# FM110236A.net
KiCad netlist of a schematic drawn in Altium Designer
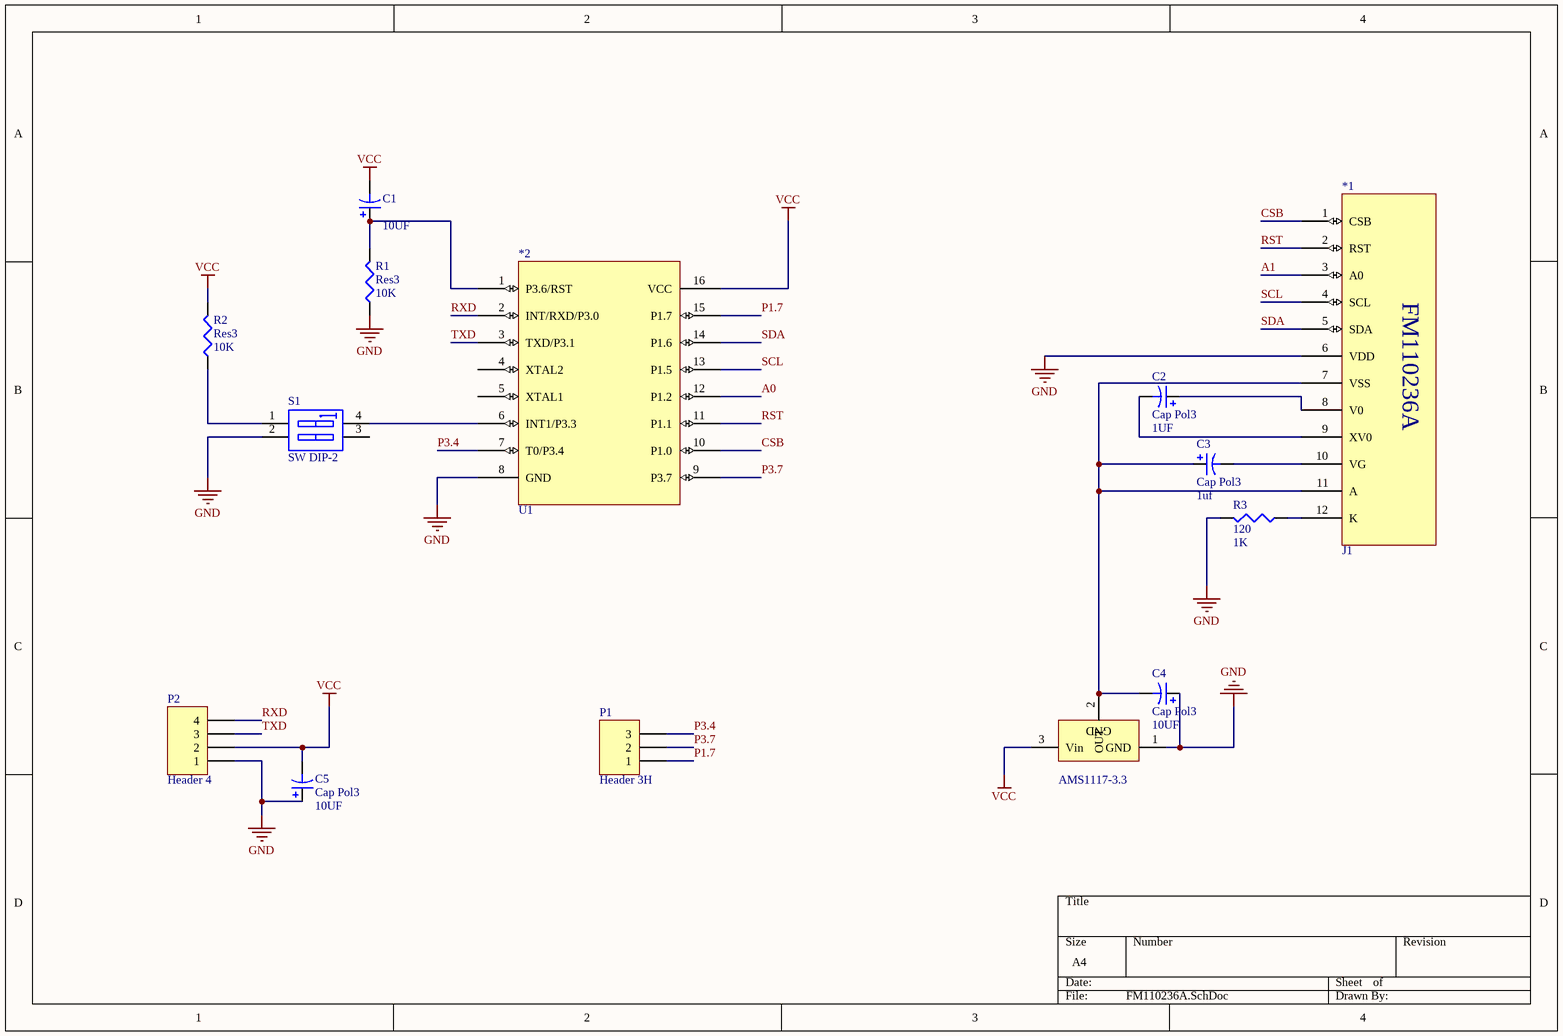
[diagram p0: FM110236A.SchDoc]

(export (version "E")
  (design (tool "Eeschema 10.0.6"))
  (components
    (comp (ref "*1")
      (value "J1")
      (footprint "PCBComponent_1")
      (libsource (lib "FM110236A") (part "Component_1"))
    )
    (comp (ref "*2")
      (value "U1")
      (footprint "TSOP127P620X160-16N")
      (libsource (lib "stc11f02") (part "Component_3"))
    )
    (comp (ref "C1")
      (value "10UF")
      (footprint "C0805")
      (description "Polarized Capacitor (Surface Mount)")
      (fields (field (name "PUBLISHER") "Altium Limited"))
      (libsource (lib "Miscellaneous Devices") (part "Cap Pol3"))
    )
    (comp (ref "C2")
      (value "Cap Pol3")
      (footprint "C0805")
      (description "Polarized Capacitor (Surface Mount)")
      (fields (field (name "ALTIUM_VALUE") "1UF") (field (name "PUBLISHER") "Altium Limited"))
      (libsource (lib "Miscellaneous Devices") (part "Cap Pol3"))
    )
    (comp (ref "C3")
      (value "Cap Pol3")
      (footprint "C0805")
      (description "Polarized Capacitor (Surface Mount)")
      (fields (field (name "ALTIUM_VALUE") "1uf") (field (name "PUBLISHER") "Altium Limited"))
      (libsource (lib "Miscellaneous Devices") (part "Cap Pol3"))
    )
    (comp (ref "C4")
      (value "Cap Pol3")
      (footprint "C0805")
      (description "Polarized Capacitor (Surface Mount)")
      (fields (field (name "ALTIUM_VALUE") "10UF") (field (name "PUBLISHER") "Altium Limited"))
      (libsource (lib "Miscellaneous Devices") (part "Cap Pol3"))
    )
    (comp (ref "C5")
      (value "Cap Pol3")
      (footprint "C0805")
      (description "Polarized Capacitor (Surface Mount)")
      (fields (field (name "ALTIUM_VALUE") "10UF") (field (name "PUBLISHER") "Altium Limited"))
      (libsource (lib "Miscellaneous Devices") (part "Cap Pol3"))
    )
    (comp (ref "P1")
      (value "Header 3H")
      (footprint "HDR1X3H")
      (description "Header, 3-Pin, Right Angle")
      (fields (field (name "PUBLISHER") "Altium Limited"))
      (libsource (lib "Miscellaneous Connectors") (part "Header 3H"))
    )
    (comp (ref "P2")
      (value "Header 4")
      (footprint "HDR1X4")
      (description "Header, 4-Pin")
      (fields (field (name "PUBLISHER") "Altium Limited"))
      (libsource (lib "Miscellaneous Connectors") (part "Header 4"))
    )
    (comp (ref "R1")
      (value "Res3")
      (footprint "J1-0603")
      (description "Resistor")
      (fields (field (name "ALTIUM_VALUE") "10K") (field (name "PUBLISHER") "Altium Limited"))
      (libsource (lib "Miscellaneous Devices") (part "Res3"))
    )
    (comp (ref "R2")
      (value "Res3")
      (footprint "J1-0603")
      (description "Resistor")
      (fields (field (name "ALTIUM_VALUE") "10K") (field (name "PUBLISHER") "Altium Limited"))
      (libsource (lib "Miscellaneous Devices") (part "Res3"))
    )
    (comp (ref "R3")
      (value "120")
      (footprint "J1-0603")
      (description "Resistor")
      (fields (field (name "ALTIUM_VALUE") "1K") (field (name "PUBLISHER") "Altium Limited"))
      (libsource (lib "Miscellaneous Devices") (part "Res3"))
    )
    (comp (ref "S1")
      (value "SW DIP-2")
      (footprint "DIP-4")
      (description "DIP Switch, 2 Position, SPST")
      (fields (field (name "PUBLISHER") "Altium Limited"))
      (libsource (lib "Miscellaneous Devices") (part "SW DIP-2"))
    )
    (comp (ref "VR1")
      (value "AMS1117-3.3")
      (footprint "SOT223_L")
      (description "Voltage Regulator")
      (fields (field (name "PUBLISHER") "Altium Limited"))
      (libsource (lib "Miscellaneous Devices") (part "Volt Reg"))
    )
  )
  (nets
    (net (code "1") (name "/A0") (class "Default")
      (node (ref "*2") (pin "12") (pinfunction "P1.2_12") (pintype "bidirectional"))
    )
    (net (code "2") (name "/A1") (class "Default")
      (node (ref "*1") (pin "3") (pinfunction "A0_3") (pintype "bidirectional"))
    )
    (net (code "3") (name "/CSB") (class "Default")
      (node (ref "*1") (pin "1") (pinfunction "CSB_1") (pintype "bidirectional"))
      (node (ref "*2") (pin "10") (pinfunction "P1.0_10") (pintype "bidirectional"))
    )
    (net (code "4") (name "/P1.7") (class "Default")
      (node (ref "*2") (pin "15") (pinfunction "P1.7_15") (pintype "bidirectional"))
      (node (ref "P1") (pin "1") (pinfunction "1_1") (pintype "passive"))
    )
    (net (code "5") (name "/P3.4") (class "Default")
      (node (ref "*2") (pin "7") (pinfunction "T0/P3.4_7") (pintype "bidirectional"))
      (node (ref "P1") (pin "3") (pinfunction "3_3") (pintype "passive"))
    )
    (net (code "6") (name "/P3.7") (class "Default")
      (node (ref "*2") (pin "9") (pinfunction "P3.7_9") (pintype "bidirectional"))
      (node (ref "P1") (pin "2") (pinfunction "2_2") (pintype "passive"))
    )
    (net (code "7") (name "/RST") (class "Default")
      (node (ref "*1") (pin "2") (pinfunction "RST_2") (pintype "bidirectional"))
      (node (ref "*2") (pin "11") (pinfunction "P1.1_11") (pintype "bidirectional"))
    )
    (net (code "8") (name "/RXD") (class "Default")
      (node (ref "*2") (pin "2") (pinfunction "INT/RXD/P3.0_2") (pintype "bidirectional"))
      (node (ref "P2") (pin "4") (pinfunction "4_4") (pintype "passive"))
    )
    (net (code "9") (name "/SCL") (class "Default")
      (node (ref "*1") (pin "4") (pinfunction "SCL_4") (pintype "bidirectional"))
      (node (ref "*2") (pin "13") (pinfunction "P1.5_13") (pintype "bidirectional"))
    )
    (net (code "10") (name "/SDA") (class "Default")
      (node (ref "*1") (pin "5") (pinfunction "SDA_5") (pintype "bidirectional"))
      (node (ref "*2") (pin "14") (pinfunction "P1.6_14") (pintype "bidirectional"))
    )
    (net (code "11") (name "/TXD") (class "Default")
      (node (ref "*2") (pin "3") (pinfunction "TXD/P3.1_3") (pintype "bidirectional"))
      (node (ref "P2") (pin "3") (pinfunction "3_3") (pintype "passive"))
    )
    (net (code "12") (name "GND") (class "Default")
      (node (ref "*1") (pin "6") (pinfunction "VDD_6") (pintype "power_in"))
      (node (ref "*2") (pin "8") (pinfunction "GND_8") (pintype "power_in"))
      (node (ref "C4") (pin "1") (pinfunction "1_1") (pintype "passive"))
      (node (ref "C5") (pin "1") (pinfunction "1_1") (pintype "passive"))
      (node (ref "P2") (pin "1") (pinfunction "1_1") (pintype "passive"))
      (node (ref "R1") (pin "1") (pinfunction "1_1") (pintype "passive"))
      (node (ref "R3") (pin "2") (pinfunction "2_2") (pintype "passive"))
      (node (ref "S1") (pin "2") (pinfunction "A2_2") (pintype "passive"))
      (node (ref "VR1") (pin "1") (pinfunction "GND_1") (pintype "power_in"))
    )
    (net (code "13") (name "Net-(*1-A)") (class "Default")
      (node (ref "*1") (pin "11") (pinfunction "A_11") (pintype "power_in"))
      (node (ref "*1") (pin "7") (pinfunction "VSS_7") (pintype "power_in"))
      (node (ref "C3") (pin "1") (pinfunction "1_1") (pintype "passive"))
      (node (ref "C4") (pin "2") (pinfunction "2_2") (pintype "passive"))
      (node (ref "VR1") (pin "2") (pinfunction "OUT_2") (pintype "power_in"))
    )
    (net (code "14") (name "Net-(*1-K)") (class "Default")
      (node (ref "*1") (pin "12") (pinfunction "K_12") (pintype "power_in"))
      (node (ref "R3") (pin "1") (pinfunction "1_1") (pintype "passive"))
    )
    (net (code "15") (name "Net-(*1-V0)") (class "Default")
      (node (ref "*1") (pin "8") (pinfunction "V0_8") (pintype "power_in"))
      (node (ref "C2") (pin "1") (pinfunction "1_1") (pintype "passive"))
    )
    (net (code "16") (name "Net-(*1-VG)") (class "Default")
      (node (ref "*1") (pin "10") (pinfunction "VG_10") (pintype "power_in"))
      (node (ref "C3") (pin "2") (pinfunction "2_2") (pintype "passive"))
    )
    (net (code "17") (name "Net-(*1-XV0)") (class "Default")
      (node (ref "*1") (pin "9") (pinfunction "XV0_9") (pintype "power_in"))
      (node (ref "C2") (pin "2") (pinfunction "2_2") (pintype "passive"))
    )
    (net (code "18") (name "Net-(*2-INT1{slash}P3.3)") (class "Default")
      (node (ref "*2") (pin "6") (pinfunction "INT1/P3.3_6") (pintype "bidirectional"))
      (node (ref "S1") (pin "4") (pinfunction "B1_4") (pintype "passive"))
    )
    (net (code "19") (name "Net-(*2-P3.6{slash}RST)") (class "Default")
      (node (ref "*2") (pin "1") (pinfunction "P3.6/RST_1") (pintype "bidirectional"))
      (node (ref "C1") (pin "1") (pinfunction "1_1") (pintype "passive"))
      (node (ref "R1") (pin "2") (pinfunction "2_2") (pintype "passive"))
    )
    (net (code "20") (name "Net-(S1-A1)") (class "Default")
      (node (ref "R2") (pin "1") (pinfunction "1_1") (pintype "passive"))
      (node (ref "S1") (pin "1") (pinfunction "A1_1") (pintype "passive"))
    )
    (net (code "21") (name "VCC") (class "Default")
      (node (ref "*2") (pin "16") (pinfunction "VCC_16") (pintype "power_in"))
      (node (ref "C1") (pin "2") (pinfunction "2_2") (pintype "passive"))
      (node (ref "C5") (pin "2") (pinfunction "2_2") (pintype "passive"))
      (node (ref "P2") (pin "2") (pinfunction "2_2") (pintype "passive"))
      (node (ref "R2") (pin "2") (pinfunction "2_2") (pintype "passive"))
      (node (ref "VR1") (pin "3") (pinfunction "Vin_3") (pintype "power_in"))
    )
    (net (code "22") (name "unconnected-(*2-XTAL1-Pad5)") (class "Default")
      (node (ref "*2") (pin "5") (pinfunction "XTAL1_5") (pintype "bidirectional"))
    )
    (net (code "23") (name "unconnected-(*2-XTAL2-Pad4)") (class "Default")
      (node (ref "*2") (pin "4") (pinfunction "XTAL2_4") (pintype "bidirectional"))
    )
    (net (code "24") (name "unconnected-(S1-B2-Pad3)") (class "Default")
      (node (ref "S1") (pin "3") (pinfunction "B2_3") (pintype "passive"))
    )
  )
)
